# PWM_OUT.net
KiCad netlist of a schematic drawn in Altium Designer
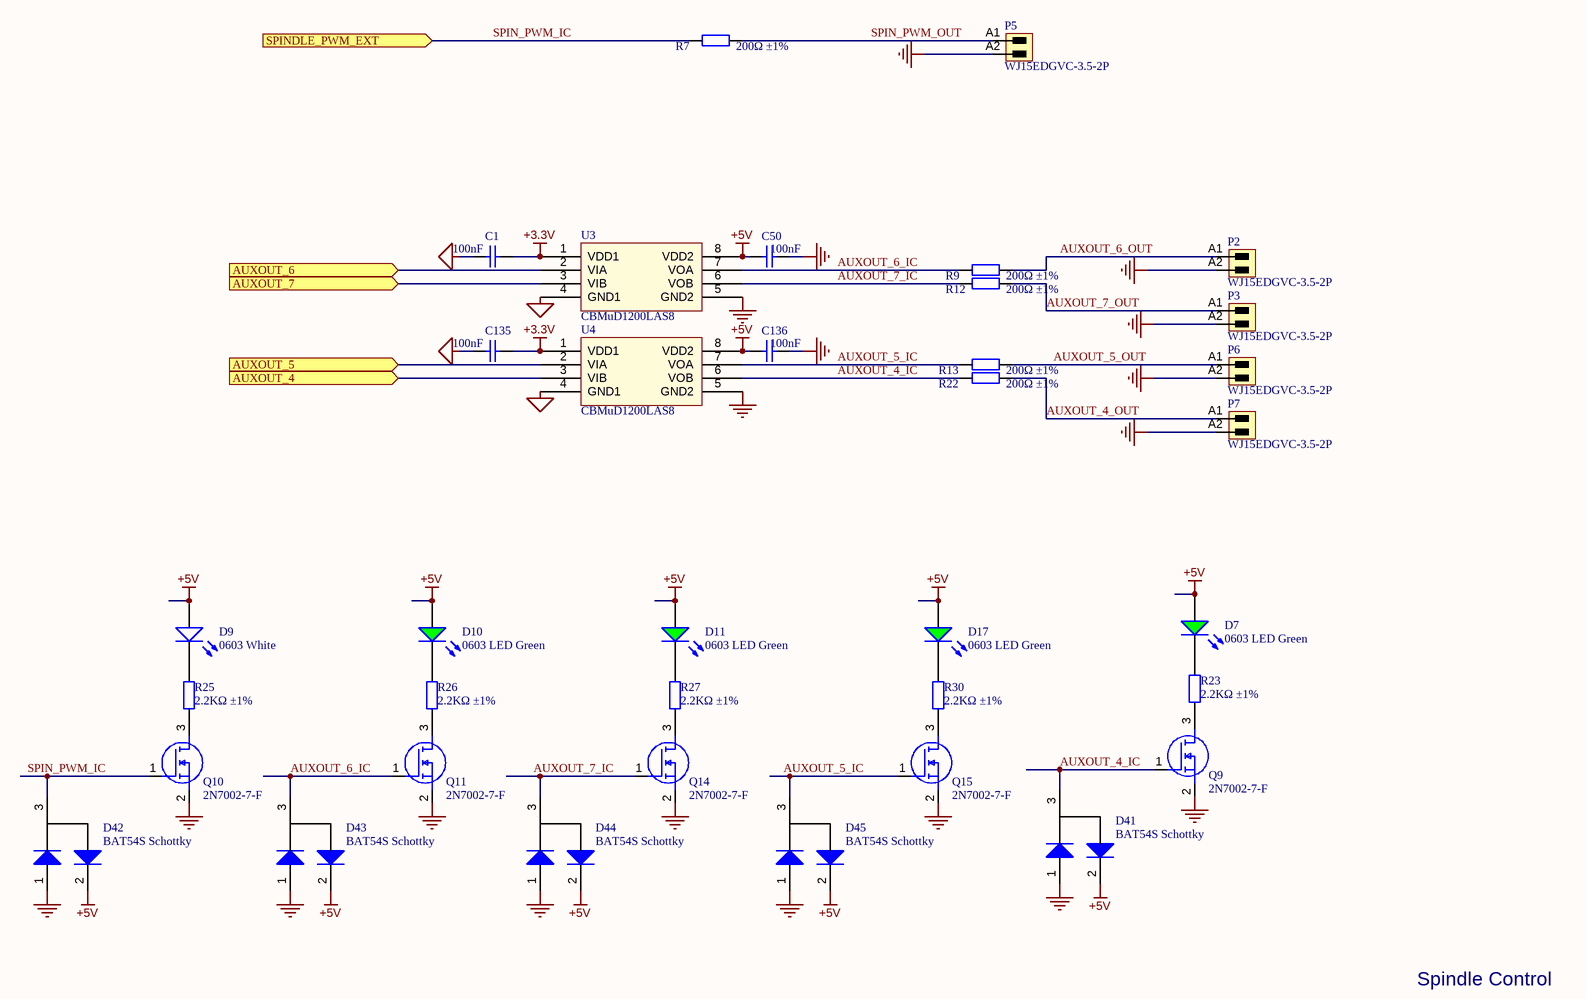
[diagram p0: PWM_OUT.SchDoc]

(export (version "E")
  (design (tool "Eeschema 10.0.6"))
  (components
    (comp (ref "C1")
      (value "100nF")
      (footprint "0402_C")
      (description "Chip capacitors")
      (fields
        (field (name "MANUFACTURER") "Samsung Electro-Mechanics")
        (field (name "PARTNUMBER") "CL05B104KO5NNNC")
      )
      (libsource (lib "Cap") (part "0402 100nF (104) 10% 16V"))
    )
    (comp (ref "C50")
      (value "100nF")
      (footprint "0402_C")
      (description "Chip capacitors")
      (fields
        (field (name "MANUFACTURER") "Samsung Electro-Mechanics")
        (field (name "PARTNUMBER") "CL05B104KO5NNNC")
      )
      (libsource (lib "Cap") (part "0402 100nF (104) 10% 16V"))
    )
    (comp (ref "C135")
      (value "100nF")
      (footprint "0402_C")
      (description "Chip capacitors")
      (fields
        (field (name "MANUFACTURER") "Samsung Electro-Mechanics")
        (field (name "PARTNUMBER") "CL05B104KO5NNNC")
      )
      (libsource (lib "Cap") (part "0402 100nF (104) 10% 16V"))
    )
    (comp (ref "C136")
      (value "100nF")
      (footprint "0402_C")
      (description "Chip capacitors")
      (fields
        (field (name "MANUFACTURER") "Samsung Electro-Mechanics")
        (field (name "PARTNUMBER") "CL05B104KO5NNNC")
      )
      (libsource (lib "Cap") (part "0402 100nF (104) 10% 16V"))
    )
    (comp (ref "D7")
      (value "0603 LED Green")
      (footprint "0603_LED_S1 - GREEN")
      (fields
        (field (name "MANUFACTURER PART NUMBER") "19-217/GHC-YR1S2/3T")
        (field (name "MANUFACTURER") "Everlight Elec")
      )
      (libsource (lib "Sienci_Labs") (part "19-217/GHC-YR1S2/3T"))
    )
    (comp (ref "D9")
      (value "0603 White")
      (footprint "0603_LED_S1 - white")
      (description "LED")
      (libsource (lib "Sienci_Labs") (part "0603 LED White"))
    )
    (comp (ref "D10")
      (value "0603 LED Green")
      (footprint "0603_LED_S1 - GREEN")
      (fields
        (field (name "MANUFACTURER PART NUMBER") "19-217/GHC-YR1S2/3T")
        (field (name "MANUFACTURER") "Everlight Elec")
      )
      (libsource (lib "Sienci_Labs") (part "19-217/GHC-YR1S2/3T"))
    )
    (comp (ref "D11")
      (value "0603 LED Green")
      (footprint "0603_LED_S1 - GREEN")
      (fields
        (field (name "MANUFACTURER PART NUMBER") "19-217/GHC-YR1S2/3T")
        (field (name "MANUFACTURER") "Everlight Elec")
      )
      (libsource (lib "Sienci_Labs") (part "19-217/GHC-YR1S2/3T"))
    )
    (comp (ref "D17")
      (value "0603 LED Green")
      (footprint "0603_LED_S1 - GREEN")
      (fields
        (field (name "MANUFACTURER PART NUMBER") "19-217/GHC-YR1S2/3T")
        (field (name "MANUFACTURER") "Everlight Elec")
      )
      (libsource (lib "Sienci_Labs") (part "19-217/GHC-YR1S2/3T"))
    )
    (comp (ref "D41")
      (value "BAT54S Schottky")
      (footprint "SOT-23(SOT-23-3)")
      (description "30V Dual 200mA 800mV@100mA SOT-23 Schottky Barrier Diodes (SBD) ROHS")
      (libsource (lib "Diode") (part "SOT-23 BAT54S"))
    )
    (comp (ref "D42")
      (value "BAT54S Schottky")
      (footprint "SOT-23(SOT-23-3)")
      (description "30V Dual 200mA 800mV@100mA SOT-23 Schottky Barrier Diodes (SBD) ROHS")
      (libsource (lib "Diode") (part "SOT-23 BAT54S"))
    )
    (comp (ref "D43")
      (value "BAT54S Schottky")
      (footprint "SOT-23(SOT-23-3)")
      (description "30V Dual 200mA 800mV@100mA SOT-23 Schottky Barrier Diodes (SBD) ROHS")
      (libsource (lib "Diode") (part "SOT-23 BAT54S"))
    )
    (comp (ref "D44")
      (value "BAT54S Schottky")
      (footprint "SOT-23(SOT-23-3)")
      (description "30V Dual 200mA 800mV@100mA SOT-23 Schottky Barrier Diodes (SBD) ROHS")
      (libsource (lib "Diode") (part "SOT-23 BAT54S"))
    )
    (comp (ref "D45")
      (value "BAT54S Schottky")
      (footprint "SOT-23(SOT-23-3)")
      (description "30V Dual 200mA 800mV@100mA SOT-23 Schottky Barrier Diodes (SBD) ROHS")
      (libsource (lib "Diode") (part "SOT-23 BAT54S"))
    )
    (comp (ref "P2")
      (value "WJ15EDGVC-3.5-2P")
      (footprint "691321100002")
      (fields (field (name "MANUFACTURER") "Weidmueller"))
      (libsource (lib "Universal_CNC_Breakout") (part "3.5mm Terminal Header 2p"))
    )
    (comp (ref "P3")
      (value "WJ15EDGVC-3.5-2P")
      (footprint "691321100002")
      (fields (field (name "MANUFACTURER") "Weidmueller"))
      (libsource (lib "Universal_CNC_Breakout") (part "3.5mm Terminal Header 2p"))
    )
    (comp (ref "P5")
      (value "WJ15EDGVC-3.5-2P")
      (footprint "691321100002")
      (fields (field (name "MANUFACTURER") "Weidmueller"))
      (libsource (lib "Universal_CNC_Breakout") (part "3.5mm Terminal Header 2p"))
    )
    (comp (ref "P6")
      (value "WJ15EDGVC-3.5-2P")
      (footprint "691321100002")
      (fields (field (name "MANUFACTURER") "Weidmueller"))
      (libsource (lib "Universal_CNC_Breakout") (part "3.5mm Terminal Header 2p"))
    )
    (comp (ref "P7")
      (value "WJ15EDGVC-3.5-2P")
      (footprint "691321100002")
      (fields (field (name "MANUFACTURER") "Weidmueller"))
      (libsource (lib "Universal_CNC_Breakout") (part "3.5mm Terminal Header 2p"))
    )
    (comp (ref "Q9")
      (value "2N7002-7-F")
      (footprint "SOT-23(SOT-23-3)")
      (description "60V 115mA 7.5Ω@5V,50mA 370mW N Channel SOT-23 MOSFETs ROHS")
      (fields (field (name "MANUFACTURER") "Diodes Inc.") (field (name "MOUSER PART NUMBER") "621-2N7002-F"))
      (libsource (lib "Sienci_Labs") (part "2N7002-7-F"))
    )
    (comp (ref "Q10")
      (value "2N7002-7-F")
      (footprint "SOT-23(SOT-23-3)")
      (description "60V 115mA 7.5Ω@5V,50mA 370mW N Channel SOT-23 MOSFETs ROHS")
      (fields (field (name "MANUFACTURER") "Diodes Inc.") (field (name "MOUSER PART NUMBER") "621-2N7002-F"))
      (libsource (lib "Sienci_Labs") (part "2N7002-7-F"))
    )
    (comp (ref "Q11")
      (value "2N7002-7-F")
      (footprint "SOT-23(SOT-23-3)")
      (description "60V 115mA 7.5Ω@5V,50mA 370mW N Channel SOT-23 MOSFETs ROHS")
      (fields (field (name "MANUFACTURER") "Diodes Inc.") (field (name "MOUSER PART NUMBER") "621-2N7002-F"))
      (libsource (lib "Sienci_Labs") (part "2N7002-7-F"))
    )
    (comp (ref "Q14")
      (value "2N7002-7-F")
      (footprint "SOT-23(SOT-23-3)")
      (description "60V 115mA 7.5Ω@5V,50mA 370mW N Channel SOT-23 MOSFETs ROHS")
      (fields (field (name "MANUFACTURER") "Diodes Inc.") (field (name "MOUSER PART NUMBER") "621-2N7002-F"))
      (libsource (lib "Sienci_Labs") (part "2N7002-7-F"))
    )
    (comp (ref "Q15")
      (value "2N7002-7-F")
      (footprint "SOT-23(SOT-23-3)")
      (description "60V 115mA 7.5Ω@5V,50mA 370mW N Channel SOT-23 MOSFETs ROHS")
      (fields (field (name "MANUFACTURER") "Diodes Inc.") (field (name "MOUSER PART NUMBER") "621-2N7002-F"))
      (libsource (lib "Sienci_Labs") (part "2N7002-7-F"))
    )
    (comp (ref "R7")
      (value "200Ω ±1%")
      (footprint "0402_R")
      (description "Chip resistor")
      (fields (field (name "MANUFACTURER") "Uniroyal Elec") (field (name "PARTNUMBER") "0402WGF2000TCE"))
      (libsource (lib "RES") (part "0402 200R (2000) 1%"))
    )
    (comp (ref "R9")
      (value "200Ω ±1%")
      (footprint "0402_R")
      (description "Chip resistor")
      (fields (field (name "MANUFACTURER") "Uniroyal Elec") (field (name "PARTNUMBER") "0402WGF2000TCE"))
      (libsource (lib "RES") (part "0402 200R (2000) 1%"))
    )
    (comp (ref "R12")
      (value "200Ω ±1%")
      (footprint "0402_R")
      (description "Chip resistor")
      (fields (field (name "MANUFACTURER") "Uniroyal Elec") (field (name "PARTNUMBER") "0402WGF2000TCE"))
      (libsource (lib "RES") (part "0402 200R (2000) 1%"))
    )
    (comp (ref "R13")
      (value "200Ω ±1%")
      (footprint "0402_R")
      (description "Chip resistor")
      (fields (field (name "MANUFACTURER") "Uniroyal Elec") (field (name "PARTNUMBER") "0402WGF2000TCE"))
      (libsource (lib "RES") (part "0402 200R (2000) 1%"))
    )
    (comp (ref "R22")
      (value "200Ω ±1%")
      (footprint "0402_R")
      (description "Chip resistor")
      (fields (field (name "MANUFACTURER") "Uniroyal Elec") (field (name "PARTNUMBER") "0402WGF2000TCE"))
      (libsource (lib "RES") (part "0402 200R (2000) 1%"))
    )
    (comp (ref "R23")
      (value "2.2KΩ ±1%")
      (footprint "0402_R")
      (description "Chip resistor")
      (fields (field (name "MANUFACTURER") "Uniroyal Elec") (field (name "POWER") "1/16W"))
      (libsource (lib "RES") (part "0402 2.2K (2201) 1%"))
    )
    (comp (ref "R25")
      (value "2.2KΩ ±1%")
      (footprint "0402_R")
      (description "Chip resistor")
      (fields (field (name "MANUFACTURER") "Uniroyal Elec") (field (name "POWER") "1/16W"))
      (libsource (lib "RES") (part "0402 2.2K (2201) 1%"))
    )
    (comp (ref "R26")
      (value "2.2KΩ ±1%")
      (footprint "0402_R")
      (description "Chip resistor")
      (fields (field (name "MANUFACTURER") "Uniroyal Elec") (field (name "POWER") "1/16W"))
      (libsource (lib "RES") (part "0402 2.2K (2201) 1%"))
    )
    (comp (ref "R27")
      (value "2.2KΩ ±1%")
      (footprint "0402_R")
      (description "Chip resistor")
      (fields (field (name "MANUFACTURER") "Uniroyal Elec") (field (name "POWER") "1/16W"))
      (libsource (lib "RES") (part "0402 2.2K (2201) 1%"))
    )
    (comp (ref "R30")
      (value "2.2KΩ ±1%")
      (footprint "0402_R")
      (description "Chip resistor")
      (fields (field (name "MANUFACTURER") "Uniroyal Elec") (field (name "POWER") "1/16W"))
      (libsource (lib "RES") (part "0402 2.2K (2201) 1%"))
    )
    (comp (ref "U3")
      (value "CBMuD1200LAS8")
      (footprint "SOIC-8_150mil")
      (description "Dual Channel Isolator")
      (libsource (lib "IC") (part "CBMuD1200LAS8"))
    )
    (comp (ref "U4")
      (value "CBMuD1200LAS8")
      (footprint "SOIC-8_150mil")
      (description "Dual Channel Isolator")
      (libsource (lib "IC") (part "CBMuD1200LAS8"))
    )
  )
  (nets
    (net (code "1") (name "+3.3V") (class "Default")
      (node (ref "C1") (pin "1") (pinfunction "1_1") (pintype "passive"))
      (node (ref "C135") (pin "1") (pinfunction "1_1") (pintype "passive"))
      (node (ref "U3") (pin "1") (pinfunction "VDD1_1") (pintype "passive"))
      (node (ref "U4") (pin "1") (pinfunction "VDD1_1") (pintype "passive"))
    )
    (net (code "2") (name "+5V") (class "Default")
      (node (ref "C136") (pin "2") (pinfunction "2_2") (pintype "passive"))
      (node (ref "C50") (pin "2") (pinfunction "2_2") (pintype "passive"))
      (node (ref "D10") (pin "A") (pinfunction "A_A") (pintype "passive"))
      (node (ref "D11") (pin "A") (pinfunction "A_A") (pintype "passive"))
      (node (ref "D17") (pin "A") (pinfunction "A_A") (pintype "passive"))
      (node (ref "D41") (pin "2") (pinfunction "A_2") (pintype "passive"))
      (node (ref "D42") (pin "2") (pinfunction "A_2") (pintype "passive"))
      (node (ref "D43") (pin "2") (pinfunction "A_2") (pintype "passive"))
      (node (ref "D44") (pin "2") (pinfunction "A_2") (pintype "passive"))
      (node (ref "D45") (pin "2") (pinfunction "A_2") (pintype "passive"))
      (node (ref "D7") (pin "A") (pinfunction "A_A") (pintype "passive"))
      (node (ref "D9") (pin "A") (pinfunction "A_A") (pintype "passive"))
      (node (ref "U3") (pin "8") (pinfunction "VDD2_8") (pintype "passive"))
      (node (ref "U4") (pin "8") (pinfunction "VDD2_8") (pintype "passive"))
    )
    (net (code "3") (name "/AUXOUT_4") (class "Default")
      (node (ref "U4") (pin "3") (pinfunction "VIB_3") (pintype "passive"))
    )
    (net (code "4") (name "/AUXOUT_4_IC") (class "Default")
      (node (ref "D41") (pin "3") (pinfunction "K_3") (pintype "passive"))
      (node (ref "Q9") (pin "1") (pinfunction "G_1") (pintype "passive"))
      (node (ref "R22") (pin "1") (pinfunction "1_1") (pintype "passive"))
      (node (ref "U4") (pin "6") (pinfunction "VOB_6") (pintype "passive"))
    )
    (net (code "5") (name "/AUXOUT_4_OUT") (class "Default")
      (node (ref "P7") (pin "A1") (pinfunction "A1_A1") (pintype "passive"))
      (node (ref "R22") (pin "2") (pinfunction "2_2") (pintype "passive"))
    )
    (net (code "6") (name "/AUXOUT_5") (class "Default")
      (node (ref "U4") (pin "2") (pinfunction "VIA_2") (pintype "passive"))
    )
    (net (code "7") (name "/AUXOUT_5_IC") (class "Default")
      (node (ref "D45") (pin "3") (pinfunction "K_3") (pintype "passive"))
      (node (ref "Q15") (pin "1") (pinfunction "G_1") (pintype "passive"))
      (node (ref "R13") (pin "1") (pinfunction "1_1") (pintype "passive"))
      (node (ref "U4") (pin "7") (pinfunction "VOA_7") (pintype "passive"))
    )
    (net (code "8") (name "/AUXOUT_5_OUT") (class "Default")
      (node (ref "P6") (pin "A1") (pinfunction "A1_A1") (pintype "passive"))
      (node (ref "R13") (pin "2") (pinfunction "2_2") (pintype "passive"))
    )
    (net (code "9") (name "/AUXOUT_6") (class "Default")
      (node (ref "U3") (pin "2") (pinfunction "VIA_2") (pintype "passive"))
    )
    (net (code "10") (name "/AUXOUT_6_IC") (class "Default")
      (node (ref "D43") (pin "3") (pinfunction "K_3") (pintype "passive"))
      (node (ref "Q11") (pin "1") (pinfunction "G_1") (pintype "passive"))
      (node (ref "R9") (pin "1") (pinfunction "1_1") (pintype "passive"))
      (node (ref "U3") (pin "7") (pinfunction "VOA_7") (pintype "passive"))
    )
    (net (code "11") (name "/AUXOUT_6_OUT") (class "Default")
      (node (ref "P2") (pin "A1") (pinfunction "A1_A1") (pintype "passive"))
      (node (ref "R9") (pin "2") (pinfunction "2_2") (pintype "passive"))
    )
    (net (code "12") (name "/AUXOUT_7") (class "Default")
      (node (ref "U3") (pin "3") (pinfunction "VIB_3") (pintype "passive"))
    )
    (net (code "13") (name "/AUXOUT_7_IC") (class "Default")
      (node (ref "D44") (pin "3") (pinfunction "K_3") (pintype "passive"))
      (node (ref "Q14") (pin "1") (pinfunction "G_1") (pintype "passive"))
      (node (ref "R12") (pin "1") (pinfunction "1_1") (pintype "passive"))
      (node (ref "U3") (pin "6") (pinfunction "VOB_6") (pintype "passive"))
    )
    (net (code "14") (name "/AUXOUT_7_OUT") (class "Default")
      (node (ref "P3") (pin "A1") (pinfunction "A1_A1") (pintype "passive"))
      (node (ref "R12") (pin "2") (pinfunction "2_2") (pintype "passive"))
    )
    (net (code "15") (name "/SPIN_PWM_IC") (class "Default")
      (node (ref "D42") (pin "3") (pinfunction "K_3") (pintype "passive"))
      (node (ref "Q10") (pin "1") (pinfunction "G_1") (pintype "passive"))
      (node (ref "R7") (pin "1") (pinfunction "1_1") (pintype "passive"))
    )
    (net (code "16") (name "/SPIN_PWM_OUT") (class "Default")
      (node (ref "P5") (pin "A1") (pinfunction "A1_A1") (pintype "passive"))
      (node (ref "R7") (pin "2") (pinfunction "2_2") (pintype "passive"))
    )
    (net (code "17") (name "GND") (class "Default")
      (node (ref "C136") (pin "1") (pinfunction "1_1") (pintype "passive"))
      (node (ref "C50") (pin "1") (pinfunction "1_1") (pintype "passive"))
      (node (ref "D41") (pin "1") (pinfunction "A_1") (pintype "passive"))
      (node (ref "D42") (pin "1") (pinfunction "A_1") (pintype "passive"))
      (node (ref "D43") (pin "1") (pinfunction "A_1") (pintype "passive"))
      (node (ref "D44") (pin "1") (pinfunction "A_1") (pintype "passive"))
      (node (ref "D45") (pin "1") (pinfunction "A_1") (pintype "passive"))
      (node (ref "P2") (pin "A2") (pinfunction "A2_A2") (pintype "passive"))
      (node (ref "P3") (pin "A2") (pinfunction "A2_A2") (pintype "passive"))
      (node (ref "P5") (pin "A2") (pinfunction "A2_A2") (pintype "passive"))
      (node (ref "P6") (pin "A2") (pinfunction "A2_A2") (pintype "passive"))
      (node (ref "P7") (pin "A2") (pinfunction "A2_A2") (pintype "passive"))
      (node (ref "Q10") (pin "2") (pinfunction "S_2") (pintype "passive"))
      (node (ref "Q11") (pin "2") (pinfunction "S_2") (pintype "passive"))
      (node (ref "Q14") (pin "2") (pinfunction "S_2") (pintype "passive"))
      (node (ref "Q15") (pin "2") (pinfunction "S_2") (pintype "passive"))
      (node (ref "Q9") (pin "2") (pinfunction "S_2") (pintype "passive"))
      (node (ref "U3") (pin "5") (pinfunction "GND2_5") (pintype "passive"))
      (node (ref "U4") (pin "5") (pinfunction "GND2_5") (pintype "passive"))
    )
    (net (code "18") (name "MCU_GND") (class "Default")
      (node (ref "C1") (pin "2") (pinfunction "2_2") (pintype "passive"))
      (node (ref "C135") (pin "2") (pinfunction "2_2") (pintype "passive"))
      (node (ref "U3") (pin "4") (pinfunction "GND1_4") (pintype "passive"))
      (node (ref "U4") (pin "4") (pinfunction "GND1_4") (pintype "passive"))
    )
    (net (code "19") (name "Net-(D7-PadK)") (class "Default")
      (node (ref "D7") (pin "K") (pinfunction "K_K") (pintype "passive"))
      (node (ref "R23") (pin "2") (pinfunction "2_2") (pintype "passive"))
    )
    (net (code "20") (name "Net-(D9-PadK)") (class "Default")
      (node (ref "D9") (pin "K") (pinfunction "K_K") (pintype "passive"))
      (node (ref "R25") (pin "2") (pinfunction "2_2") (pintype "passive"))
    )
    (net (code "21") (name "Net-(D10-PadK)") (class "Default")
      (node (ref "D10") (pin "K") (pinfunction "K_K") (pintype "passive"))
      (node (ref "R26") (pin "2") (pinfunction "2_2") (pintype "passive"))
    )
    (net (code "22") (name "Net-(D11-PadK)") (class "Default")
      (node (ref "D11") (pin "K") (pinfunction "K_K") (pintype "passive"))
      (node (ref "R27") (pin "2") (pinfunction "2_2") (pintype "passive"))
    )
    (net (code "23") (name "Net-(D17-PadK)") (class "Default")
      (node (ref "D17") (pin "K") (pinfunction "K_K") (pintype "passive"))
      (node (ref "R30") (pin "2") (pinfunction "2_2") (pintype "passive"))
    )
    (net (code "24") (name "Net-(Q9-D)") (class "Default")
      (node (ref "Q9") (pin "3") (pinfunction "D_3") (pintype "passive"))
      (node (ref "R23") (pin "1") (pinfunction "1_1") (pintype "passive"))
    )
    (net (code "25") (name "Net-(Q10-D)") (class "Default")
      (node (ref "Q10") (pin "3") (pinfunction "D_3") (pintype "passive"))
      (node (ref "R25") (pin "1") (pinfunction "1_1") (pintype "passive"))
    )
    (net (code "26") (name "Net-(Q11-D)") (class "Default")
      (node (ref "Q11") (pin "3") (pinfunction "D_3") (pintype "passive"))
      (node (ref "R26") (pin "1") (pinfunction "1_1") (pintype "passive"))
    )
    (net (code "27") (name "Net-(Q14-D)") (class "Default")
      (node (ref "Q14") (pin "3") (pinfunction "D_3") (pintype "passive"))
      (node (ref "R27") (pin "1") (pinfunction "1_1") (pintype "passive"))
    )
    (net (code "28") (name "Net-(Q15-D)") (class "Default")
      (node (ref "Q15") (pin "3") (pinfunction "D_3") (pintype "passive"))
      (node (ref "R30") (pin "1") (pinfunction "1_1") (pintype "passive"))
    )
  )
)
